# Sheet2-edgy.net
KiCad netlist of a schematic drawn in Altium Designer
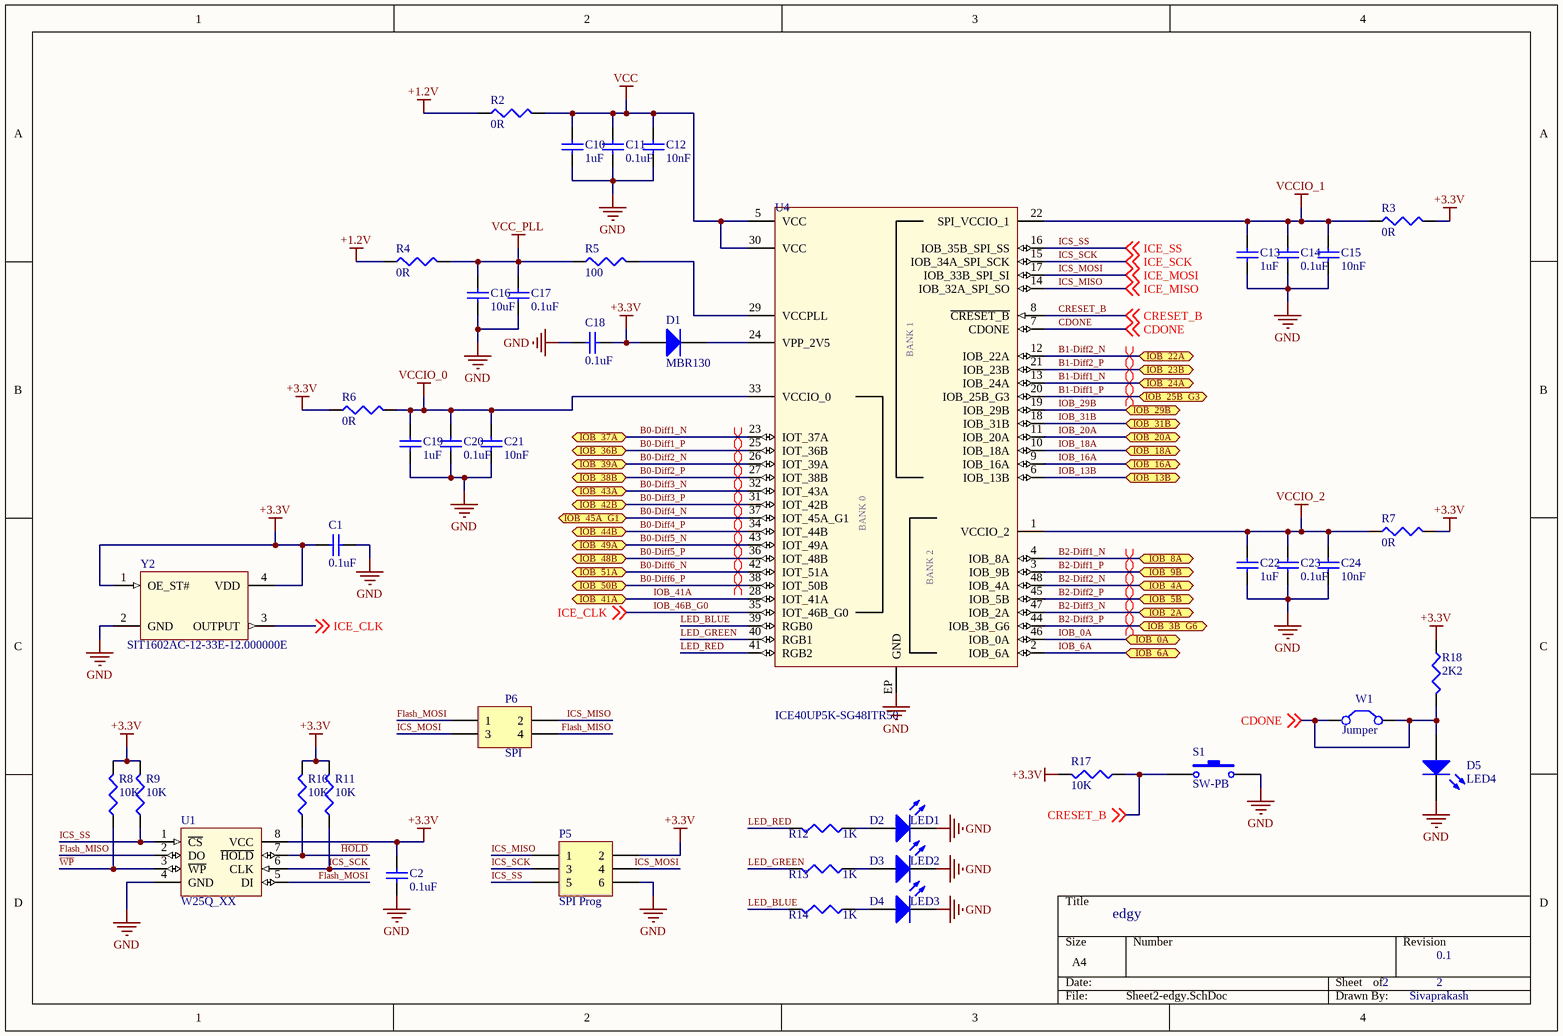
[diagram p0: Sheet2-edgy.SchDoc]

(export (version "E")
  (design (tool "Eeschema 10.0.6"))
  (components
    (comp (ref "C1")
      (value "0.1uF")
      (footprint "1608[0603]")
      (description "Capacitor (Semiconductor SIM Model)")
      (fields (field (name "PUBLISHER") "Altium Limited"))
      (libsource (lib "Miscellaneous Devices") (part "Cap Semi"))
    )
    (comp (ref "C2")
      (value "0.1uF")
      (footprint "1608[0603]")
      (description "Capacitor (Semiconductor SIM Model)")
      (fields (field (name "PUBLISHER") "Altium Limited"))
      (libsource (lib "Miscellaneous Devices") (part "Cap Semi"))
    )
    (comp (ref "C10")
      (value "1uF")
      (footprint "1608[0603]")
      (description "Capacitor (Semiconductor SIM Model)")
      (fields (field (name "PUBLISHER") "Altium Limited"))
      (libsource (lib "Miscellaneous Devices") (part "Cap Semi"))
    )
    (comp (ref "C11")
      (value "0.1uF")
      (footprint "1608[0603]")
      (description "Capacitor (Semiconductor SIM Model)")
      (fields (field (name "PUBLISHER") "Altium Limited"))
      (libsource (lib "Miscellaneous Devices") (part "Cap Semi"))
    )
    (comp (ref "C12")
      (value "10nF")
      (footprint "1608[0603]")
      (description "Capacitor (Semiconductor SIM Model)")
      (fields (field (name "PUBLISHER") "Altium Limited"))
      (libsource (lib "Miscellaneous Devices") (part "Cap Semi"))
    )
    (comp (ref "C13")
      (value "1uF")
      (footprint "1608[0603]")
      (description "Capacitor (Semiconductor SIM Model)")
      (fields (field (name "PUBLISHER") "Altium Limited"))
      (libsource (lib "Miscellaneous Devices") (part "Cap Semi"))
    )
    (comp (ref "C14")
      (value "0.1uF")
      (footprint "1608[0603]")
      (description "Capacitor (Semiconductor SIM Model)")
      (fields (field (name "PUBLISHER") "Altium Limited"))
      (libsource (lib "Miscellaneous Devices") (part "Cap Semi"))
    )
    (comp (ref "C15")
      (value "10nF")
      (footprint "1608[0603]")
      (description "Capacitor (Semiconductor SIM Model)")
      (fields (field (name "PUBLISHER") "Altium Limited"))
      (libsource (lib "Miscellaneous Devices") (part "Cap Semi"))
    )
    (comp (ref "C16")
      (value "10uF")
      (footprint "1608[0603]")
      (description "Capacitor (Semiconductor SIM Model)")
      (fields (field (name "PUBLISHER") "Altium Limited"))
      (libsource (lib "Miscellaneous Devices") (part "Cap Semi"))
    )
    (comp (ref "C17")
      (value "0.1uF")
      (footprint "1608[0603]")
      (description "Capacitor (Semiconductor SIM Model)")
      (fields (field (name "PUBLISHER") "Altium Limited"))
      (libsource (lib "Miscellaneous Devices") (part "Cap Semi"))
    )
    (comp (ref "C18")
      (value "0.1uF")
      (footprint "1608[0603]")
      (description "Capacitor (Semiconductor SIM Model)")
      (fields (field (name "PUBLISHER") "Altium Limited"))
      (libsource (lib "Miscellaneous Devices") (part "Cap Semi"))
    )
    (comp (ref "C19")
      (value "1uF")
      (footprint "1608[0603]")
      (description "Capacitor (Semiconductor SIM Model)")
      (fields (field (name "PUBLISHER") "Altium Limited"))
      (libsource (lib "Miscellaneous Devices") (part "Cap Semi"))
    )
    (comp (ref "C20")
      (value "0.1uF")
      (footprint "1608[0603]")
      (description "Capacitor (Semiconductor SIM Model)")
      (fields (field (name "PUBLISHER") "Altium Limited"))
      (libsource (lib "Miscellaneous Devices") (part "Cap Semi"))
    )
    (comp (ref "C21")
      (value "10nF")
      (footprint "1608[0603]")
      (description "Capacitor (Semiconductor SIM Model)")
      (fields (field (name "PUBLISHER") "Altium Limited"))
      (libsource (lib "Miscellaneous Devices") (part "Cap Semi"))
    )
    (comp (ref "C22")
      (value "1uF")
      (footprint "1608[0603]")
      (description "Capacitor (Semiconductor SIM Model)")
      (fields (field (name "PUBLISHER") "Altium Limited"))
      (libsource (lib "Miscellaneous Devices") (part "Cap Semi"))
    )
    (comp (ref "C23")
      (value "0.1uF")
      (footprint "1608[0603]")
      (description "Capacitor (Semiconductor SIM Model)")
      (fields (field (name "PUBLISHER") "Altium Limited"))
      (libsource (lib "Miscellaneous Devices") (part "Cap Semi"))
    )
    (comp (ref "C24")
      (value "10nF")
      (footprint "1608[0603]")
      (description "Capacitor (Semiconductor SIM Model)")
      (fields (field (name "PUBLISHER") "Altium Limited"))
      (libsource (lib "Miscellaneous Devices") (part "Cap Semi"))
    )
    (comp (ref "D1")
      (value "MBR130")
      (footprint "SOD_123")
      (description "Default Diode")
      (fields (field (name "PUBLISHER") "Altium Limited"))
      (libsource (lib "Miscellaneous Devices") (part "Diode"))
    )
    (comp (ref "D2")
      (value "LED1")
      (footprint "1608[0603]")
      (description "Typical BLUE SiC LED")
      (fields (field (name "PUBLISHER") "Altium Limited"))
      (libsource (lib "Miscellaneous Devices") (part "LED3"))
    )
    (comp (ref "D3")
      (value "LED2")
      (footprint "1608[0603]")
      (description "Typical BLUE SiC LED")
      (fields (field (name "PUBLISHER") "Altium Limited"))
      (libsource (lib "Miscellaneous Devices") (part "LED3"))
    )
    (comp (ref "D4")
      (value "LED3")
      (footprint "1608[0603]")
      (description "Typical BLUE SiC LED")
      (fields (field (name "PUBLISHER") "Altium Limited"))
      (libsource (lib "Miscellaneous Devices") (part "LED3"))
    )
    (comp (ref "D5")
      (value "LED4")
      (footprint "1608[0603]")
      (description "Typical BLUE SiC LED")
      (fields (field (name "PUBLISHER") "Altium Limited"))
      (libsource (lib "Miscellaneous Devices") (part "LED3"))
    )
    (comp (ref "P5")
      (value "SPI Prog")
      (footprint "2x3_2.54mm_pitch_header")
      (description "Header, 3-Pin, Dual row")
      (fields (field (name "PUBLISHER") "Altium Limited"))
      (libsource (lib "Miscellaneous Connectors") (part "Header 3X2"))
    )
    (comp (ref "P6")
      (value "SPI")
      (footprint "2x2_2.54mm_pitch_header")
      (description "Header, 2-Pin, Dual row")
      (fields (field (name "PUBLISHER") "Altium Limited"))
      (libsource (lib "Miscellaneous Connectors") (part "Header 2X2"))
    )
    (comp (ref "R2")
      (value "0R")
      (footprint "J1-0603")
      (description "Resistor")
      (fields (field (name "PUBLISHER") "Altium Limited"))
      (libsource (lib "Miscellaneous Devices") (part "Res3"))
    )
    (comp (ref "R3")
      (value "0R")
      (footprint "J1-0603")
      (description "Resistor")
      (fields (field (name "PUBLISHER") "Altium Limited"))
      (libsource (lib "Miscellaneous Devices") (part "Res3"))
    )
    (comp (ref "R4")
      (value "0R")
      (footprint "J1-0603")
      (description "Resistor")
      (fields (field (name "PUBLISHER") "Altium Limited"))
      (libsource (lib "Miscellaneous Devices") (part "Res3"))
    )
    (comp (ref "R5")
      (value "100")
      (footprint "J1-0603")
      (description "Resistor")
      (fields (field (name "PUBLISHER") "Altium Limited"))
      (libsource (lib "Miscellaneous Devices") (part "Res3"))
    )
    (comp (ref "R6")
      (value "0R")
      (footprint "J1-0603")
      (description "Resistor")
      (fields (field (name "PUBLISHER") "Altium Limited"))
      (libsource (lib "Miscellaneous Devices") (part "Res3"))
    )
    (comp (ref "R7")
      (value "0R")
      (footprint "J1-0603")
      (description "Resistor")
      (fields (field (name "PUBLISHER") "Altium Limited"))
      (libsource (lib "Miscellaneous Devices") (part "Res3"))
    )
    (comp (ref "R8")
      (value "10K")
      (footprint "J1-0603")
      (description "Resistor")
      (fields (field (name "PUBLISHER") "Altium Limited"))
      (libsource (lib "Miscellaneous Devices") (part "Res3"))
    )
    (comp (ref "R9")
      (value "10K")
      (footprint "J1-0603")
      (description "Resistor")
      (fields (field (name "PUBLISHER") "Altium Limited"))
      (libsource (lib "Miscellaneous Devices") (part "Res3"))
    )
    (comp (ref "R10")
      (value "10K")
      (footprint "J1-0603")
      (description "Resistor")
      (fields (field (name "PUBLISHER") "Altium Limited"))
      (libsource (lib "Miscellaneous Devices") (part "Res3"))
    )
    (comp (ref "R11")
      (value "10K")
      (footprint "J1-0603")
      (description "Resistor")
      (fields (field (name "PUBLISHER") "Altium Limited"))
      (libsource (lib "Miscellaneous Devices") (part "Res3"))
    )
    (comp (ref "R12")
      (value "1K")
      (footprint "J1-0603")
      (description "Resistor")
      (fields (field (name "PUBLISHER") "Altium Limited"))
      (libsource (lib "Miscellaneous Devices") (part "Res3"))
    )
    (comp (ref "R13")
      (value "1K")
      (footprint "J1-0603")
      (description "Resistor")
      (fields (field (name "PUBLISHER") "Altium Limited"))
      (libsource (lib "Miscellaneous Devices") (part "Res3"))
    )
    (comp (ref "R14")
      (value "1K")
      (footprint "J1-0603")
      (description "Resistor")
      (fields (field (name "PUBLISHER") "Altium Limited"))
      (libsource (lib "Miscellaneous Devices") (part "Res3"))
    )
    (comp (ref "R17")
      (value "10K")
      (footprint "J1-0603")
      (description "Resistor")
      (fields (field (name "PUBLISHER") "Altium Limited"))
      (libsource (lib "Miscellaneous Devices") (part "Res3"))
    )
    (comp (ref "R18")
      (value "2K2")
      (footprint "J1-0603")
      (description "Resistor")
      (fields (field (name "PUBLISHER") "Altium Limited"))
      (libsource (lib "Miscellaneous Devices") (part "Res3"))
    )
    (comp (ref "S1")
      (value "SW-PB")
      (footprint "Tact_Switch")
      (description "Switch")
      (fields (field (name "PUBLISHER") "Altium Limited"))
      (libsource (lib "Miscellaneous Devices") (part "SW-PB"))
    )
    (comp (ref "U1")
      (value "W25Q_XX")
      (footprint "SOIC-8_3.9x4.9mm_pitch1.27mm")
      (libsource (lib "edgy") (part "W25Q_XX"))
    )
    (comp (ref "U4")
      (value "ICE40UP5K-SG48ITR50")
      (footprint "*QFN50P700X700X100-49N_ICE40UP5K-SG48ITR50(Primary)")
      (description "iCE40 UltraPlusÂ™ 5280 LUTs 39 I/O 1.2 V Surface Mount FOPGA - QFN-48")
      (fields
        (field (name "DIGI-KEY_PART_NUMBER") "220-2145-1-ND")
        (field (name "MF") "Lattice Semiconductor")
      )
      (libsource (lib "edgy") (part "ICE40UP5K-SG48ITR50"))
    )
    (comp (ref "W1")
      (value "Jumper")
      (footprint "0402")
      (description "Jumper Wire")
      (fields (field (name "PUBLISHER") "Altium Limited"))
      (libsource (lib "Miscellaneous Devices") (part "Jumper"))
    )
    (comp (ref "Y2")
      (value "SIT1602AC-12-33E-12.000000E")
      (footprint "*OSCDFN320X250X80-4N")
      (fields (field (name "MANUFACTURER") "SiTime"))
      (libsource (lib "edgy") (part "SIT1602AC-12-33E-12.000000E"))
    )
  )
  (nets
    (net (code "1") (name "+1.2V") (class "Default")
      (node (ref "R2") (pin "1") (pinfunction "1_1") (pintype "passive"))
      (node (ref "R4") (pin "1") (pinfunction "1_1") (pintype "passive"))
    )
    (net (code "2") (name "+3.3V") (class "Default")
      (node (ref "C1") (pin "2") (pinfunction "2_2") (pintype "passive"))
      (node (ref "C18") (pin "1") (pinfunction "1_1") (pintype "passive"))
      (node (ref "C2") (pin "2") (pinfunction "2_2") (pintype "passive"))
      (node (ref "D1") (pin "1") (pinfunction "A_1") (pintype "passive"))
      (node (ref "P5") (pin "2") (pinfunction "2_2") (pintype "passive"))
      (node (ref "R10") (pin "1") (pinfunction "1_1") (pintype "passive"))
      (node (ref "R11") (pin "1") (pinfunction "1_1") (pintype "passive"))
      (node (ref "R17") (pin "2") (pinfunction "2_2") (pintype "passive"))
      (node (ref "R18") (pin "1") (pinfunction "1_1") (pintype "passive"))
      (node (ref "R3") (pin "1") (pinfunction "1_1") (pintype "passive"))
      (node (ref "R6") (pin "1") (pinfunction "1_1") (pintype "passive"))
      (node (ref "R7") (pin "1") (pinfunction "1_1") (pintype "passive"))
      (node (ref "R8") (pin "1") (pinfunction "1_1") (pintype "passive"))
      (node (ref "R9") (pin "1") (pinfunction "1_1") (pintype "passive"))
      (node (ref "U1") (pin "8") (pinfunction "VCC_8") (pintype "power_in"))
      (node (ref "Y2") (pin "1") (pinfunction "OE_ST#_1") (pintype "input"))
      (node (ref "Y2") (pin "4") (pinfunction "VDD_4") (pintype "power_in"))
    )
    (net (code "3") (name "/B0-Diff1_N") (class "Default")
      (node (ref "U4") (pin "23") (pinfunction "IOT_37A_23") (pintype "bidirectional"))
    )
    (net (code "4") (name "/B0-Diff1_P") (class "Default")
      (node (ref "U4") (pin "25") (pinfunction "IOT_36B_25") (pintype "bidirectional"))
    )
    (net (code "5") (name "/B0-Diff2_N") (class "Default")
      (node (ref "U4") (pin "26") (pinfunction "IOT_39A_26") (pintype "bidirectional"))
    )
    (net (code "6") (name "/B0-Diff2_P") (class "Default")
      (node (ref "U4") (pin "27") (pinfunction "IOT_38B_27") (pintype "bidirectional"))
    )
    (net (code "7") (name "/B0-Diff3_N") (class "Default")
      (node (ref "U4") (pin "32") (pinfunction "IOT_43A_32") (pintype "bidirectional"))
    )
    (net (code "8") (name "/B0-Diff3_P") (class "Default")
      (node (ref "U4") (pin "31") (pinfunction "IOT_42B_31") (pintype "bidirectional"))
    )
    (net (code "9") (name "/B0-Diff4_N") (class "Default")
      (node (ref "U4") (pin "37") (pinfunction "IOT_45A_G1_37") (pintype "bidirectional"))
    )
    (net (code "10") (name "/B0-Diff4_P") (class "Default")
      (node (ref "U4") (pin "34") (pinfunction "IOT_44B_34") (pintype "bidirectional"))
    )
    (net (code "11") (name "/B0-Diff5_N") (class "Default")
      (node (ref "U4") (pin "43") (pinfunction "IOT_49A_43") (pintype "bidirectional"))
    )
    (net (code "12") (name "/B0-Diff5_P") (class "Default")
      (node (ref "U4") (pin "36") (pinfunction "IOT_48B_36") (pintype "bidirectional"))
    )
    (net (code "13") (name "/B0-Diff6_N") (class "Default")
      (node (ref "U4") (pin "42") (pinfunction "IOT_51A_42") (pintype "bidirectional"))
    )
    (net (code "14") (name "/B0-Diff6_P") (class "Default")
      (node (ref "U4") (pin "38") (pinfunction "IOT_50B_38") (pintype "bidirectional"))
    )
    (net (code "15") (name "/B1-Diff1_N") (class "Default")
      (node (ref "U4") (pin "13") (pinfunction "IOB_24A_13") (pintype "bidirectional"))
    )
    (net (code "16") (name "/B1-Diff1_P") (class "Default")
      (node (ref "U4") (pin "20") (pinfunction "IOB_25B_G3_20") (pintype "bidirectional"))
    )
    (net (code "17") (name "/B1-Diff2_N") (class "Default")
      (node (ref "U4") (pin "12") (pinfunction "IOB_22A_12") (pintype "bidirectional"))
    )
    (net (code "18") (name "/B1-Diff2_P") (class "Default")
      (node (ref "U4") (pin "21") (pinfunction "IOB_23B_21") (pintype "bidirectional"))
    )
    (net (code "19") (name "/B2-Diff1_N") (class "Default")
      (node (ref "U4") (pin "4") (pinfunction "IOB_8A_4") (pintype "bidirectional"))
    )
    (net (code "20") (name "/B2-Diff1_P") (class "Default")
      (node (ref "U4") (pin "3") (pinfunction "IOB_9B_3") (pintype "bidirectional"))
    )
    (net (code "21") (name "/B2-Diff2_N") (class "Default")
      (node (ref "U4") (pin "48") (pinfunction "IOB_4A_48") (pintype "bidirectional"))
    )
    (net (code "22") (name "/B2-Diff2_P") (class "Default")
      (node (ref "U4") (pin "45") (pinfunction "IOB_5B_45") (pintype "bidirectional"))
    )
    (net (code "23") (name "/B2-Diff3_N") (class "Default")
      (node (ref "U4") (pin "47") (pinfunction "IOB_2A_47") (pintype "bidirectional"))
    )
    (net (code "24") (name "/B2-Diff3_P") (class "Default")
      (node (ref "U4") (pin "44") (pinfunction "IOB_3B_G6_44") (pintype "bidirectional"))
    )
    (net (code "25") (name "/Flash_MISO") (class "Default")
      (node (ref "P6") (pin "4") (pinfunction "4_4") (pintype "passive"))
      (node (ref "U1") (pin "2") (pinfunction "DO_2") (pintype "bidirectional"))
    )
    (net (code "26") (name "/Flash_MOSI") (class "Default")
      (node (ref "P6") (pin "1") (pinfunction "1_1") (pintype "passive"))
      (node (ref "U1") (pin "5") (pinfunction "DI_5") (pintype "bidirectional"))
    )
    (net (code "27") (name "/IOB_0A") (class "Default")
      (node (ref "U4") (pin "46") (pinfunction "IOB_0A_46") (pintype "bidirectional"))
    )
    (net (code "28") (name "/IOB_6A") (class "Default")
      (node (ref "U4") (pin "2") (pinfunction "IOB_6A_2") (pintype "bidirectional"))
    )
    (net (code "29") (name "/IOB_13B") (class "Default")
      (node (ref "U4") (pin "6") (pinfunction "IOB_13B_6") (pintype "bidirectional"))
    )
    (net (code "30") (name "/IOB_16A") (class "Default")
      (node (ref "U4") (pin "9") (pinfunction "IOB_16A_9") (pintype "bidirectional"))
    )
    (net (code "31") (name "/IOB_18A") (class "Default")
      (node (ref "U4") (pin "10") (pinfunction "IOB_18A_10") (pintype "bidirectional"))
    )
    (net (code "32") (name "/IOB_20A") (class "Default")
      (node (ref "U4") (pin "11") (pinfunction "IOB_20A_11") (pintype "bidirectional"))
    )
    (net (code "33") (name "/IOB_29B") (class "Default")
      (node (ref "U4") (pin "19") (pinfunction "IOB_29B_19") (pintype "bidirectional"))
    )
    (net (code "34") (name "/IOB_31B") (class "Default")
      (node (ref "U4") (pin "18") (pinfunction "IOB_31B_18") (pintype "bidirectional"))
    )
    (net (code "35") (name "/IOB_41A") (class "Default")
      (node (ref "U4") (pin "28") (pinfunction "IOT_41A_28") (pintype "bidirectional"))
    )
    (net (code "36") (name "/LED_BLUE") (class "Default")
      (node (ref "R14") (pin "2") (pinfunction "2_2") (pintype "passive"))
      (node (ref "U4") (pin "39") (pinfunction "RGB0_39") (pintype "bidirectional"))
    )
    (net (code "37") (name "/LED_GREEN") (class "Default")
      (node (ref "R13") (pin "2") (pinfunction "2_2") (pintype "passive"))
      (node (ref "U4") (pin "40") (pinfunction "RGB1_40") (pintype "bidirectional"))
    )
    (net (code "38") (name "/LED_RED") (class "Default")
      (node (ref "R12") (pin "2") (pinfunction "2_2") (pintype "passive"))
      (node (ref "U4") (pin "41") (pinfunction "RGB2_41") (pintype "bidirectional"))
    )
    (net (code "39") (name "/~{HOLD}") (class "Default")
      (node (ref "R10") (pin "2") (pinfunction "2_2") (pintype "passive"))
      (node (ref "U1") (pin "7") (pinfunction "~{HOLD}_7") (pintype "bidirectional"))
    )
    (net (code "40") (name "/~{WP}") (class "Default")
      (node (ref "R8") (pin "2") (pinfunction "2_2") (pintype "passive"))
      (node (ref "U1") (pin "3") (pinfunction "~{WP}_3") (pintype "bidirectional"))
    )
    (net (code "41") (name "CDONE") (class "Default")
      (node (ref "D5") (pin "1") (pinfunction "A_1") (pintype "passive"))
      (node (ref "R18") (pin "2") (pinfunction "2_2") (pintype "passive"))
      (node (ref "U4") (pin "7") (pinfunction "CDONE_7") (pintype "bidirectional"))
      (node (ref "W1") (pin "1") (pinfunction "C1_1") (pintype "passive"))
      (node (ref "W1") (pin "2") (pinfunction "C2_2") (pintype "passive"))
    )
    (net (code "42") (name "CRESET_B") (class "Default")
      (node (ref "R17") (pin "1") (pinfunction "1_1") (pintype "passive"))
      (node (ref "S1") (pin "1") (pinfunction "1_1") (pintype "passive"))
      (node (ref "U4") (pin "8") (pinfunction "~{CRESET_B}_8") (pintype "input"))
    )
    (net (code "43") (name "GND") (class "Default")
      (node (ref "C1") (pin "1") (pinfunction "1_1") (pintype "passive"))
      (node (ref "C10") (pin "1") (pinfunction "1_1") (pintype "passive"))
      (node (ref "C11") (pin "1") (pinfunction "1_1") (pintype "passive"))
      (node (ref "C12") (pin "1") (pinfunction "1_1") (pintype "passive"))
      (node (ref "C13") (pin "1") (pinfunction "1_1") (pintype "passive"))
      (node (ref "C14") (pin "1") (pinfunction "1_1") (pintype "passive"))
      (node (ref "C15") (pin "1") (pinfunction "1_1") (pintype "passive"))
      (node (ref "C16") (pin "1") (pinfunction "1_1") (pintype "passive"))
      (node (ref "C17") (pin "1") (pinfunction "1_1") (pintype "passive"))
      (node (ref "C18") (pin "2") (pinfunction "2_2") (pintype "passive"))
      (node (ref "C19") (pin "1") (pinfunction "1_1") (pintype "passive"))
      (node (ref "C2") (pin "1") (pinfunction "1_1") (pintype "passive"))
      (node (ref "C20") (pin "1") (pinfunction "1_1") (pintype "passive"))
      (node (ref "C21") (pin "1") (pinfunction "1_1") (pintype "passive"))
      (node (ref "C22") (pin "1") (pinfunction "1_1") (pintype "passive"))
      (node (ref "C23") (pin "1") (pinfunction "1_1") (pintype "passive"))
      (node (ref "C24") (pin "1") (pinfunction "1_1") (pintype "passive"))
      (node (ref "D2") (pin "2") (pinfunction "K_2") (pintype "passive"))
      (node (ref "D3") (pin "2") (pinfunction "K_2") (pintype "passive"))
      (node (ref "D4") (pin "2") (pinfunction "K_2") (pintype "passive"))
      (node (ref "D5") (pin "2") (pinfunction "K_2") (pintype "passive"))
      (node (ref "P5") (pin "6") (pinfunction "6_6") (pintype "passive"))
      (node (ref "S1") (pin "2") (pinfunction "2_2") (pintype "passive"))
      (node (ref "U1") (pin "4") (pinfunction "GND_4") (pintype "power_in"))
      (node (ref "U4") (pin "EP") (pinfunction "GND_EP") (pintype "power_in"))
      (node (ref "Y2") (pin "2") (pinfunction "GND_2") (pintype "power_in"))
    )
    (net (code "44") (name "ICE_CLK") (class "Default")
      (node (ref "U4") (pin "35") (pinfunction "IOT_46B_G0_35") (pintype "bidirectional"))
      (node (ref "Y2") (pin "3") (pinfunction "OUTPUT_3") (pintype "output"))
    )
    (net (code "45") (name "ICE_MISO") (class "Default")
      (node (ref "P5") (pin "1") (pinfunction "1_1") (pintype "passive"))
      (node (ref "P6") (pin "2") (pinfunction "2_2") (pintype "passive"))
      (node (ref "U4") (pin "14") (pinfunction "IOB_32A_SPI_SO_14") (pintype "bidirectional"))
    )
    (net (code "46") (name "ICE_MOSI") (class "Default")
      (node (ref "P5") (pin "4") (pinfunction "4_4") (pintype "passive"))
      (node (ref "P6") (pin "3") (pinfunction "3_3") (pintype "passive"))
      (node (ref "U4") (pin "17") (pinfunction "IOB_33B_SPI_SI_17") (pintype "bidirectional"))
    )
    (net (code "47") (name "ICE_SCK") (class "Default")
      (node (ref "P5") (pin "3") (pinfunction "3_3") (pintype "passive"))
      (node (ref "R11") (pin "2") (pinfunction "2_2") (pintype "passive"))
      (node (ref "U1") (pin "6") (pinfunction "CLK_6") (pintype "input"))
      (node (ref "U4") (pin "15") (pinfunction "IOB_34A_SPI_SCK_15") (pintype "bidirectional"))
    )
    (net (code "48") (name "ICE_SS") (class "Default")
      (node (ref "P5") (pin "5") (pinfunction "5_5") (pintype "passive"))
      (node (ref "R9") (pin "2") (pinfunction "2_2") (pintype "passive"))
      (node (ref "U1") (pin "1") (pinfunction "~{CS}_1") (pintype "input"))
      (node (ref "U4") (pin "16") (pinfunction "IOB_35B_SPI_SS_16") (pintype "bidirectional"))
    )
    (net (code "49") (name "Net-(D1-K)") (class "Default")
      (node (ref "D1") (pin "2") (pinfunction "K_2") (pintype "passive"))
      (node (ref "U4") (pin "24") (pinfunction "VPP_2V5_24") (pintype "power_in"))
    )
    (net (code "50") (name "Net-(D2-A)") (class "Default")
      (node (ref "D2") (pin "1") (pinfunction "A_1") (pintype "passive"))
      (node (ref "R12") (pin "1") (pinfunction "1_1") (pintype "passive"))
    )
    (net (code "51") (name "Net-(D3-A)") (class "Default")
      (node (ref "D3") (pin "1") (pinfunction "A_1") (pintype "passive"))
      (node (ref "R13") (pin "1") (pinfunction "1_1") (pintype "passive"))
    )
    (net (code "52") (name "Net-(D4-A)") (class "Default")
      (node (ref "D4") (pin "1") (pinfunction "A_1") (pintype "passive"))
      (node (ref "R14") (pin "1") (pinfunction "1_1") (pintype "passive"))
    )
    (net (code "53") (name "Net-(U4-VCCPLL)") (class "Default")
      (node (ref "R5") (pin "2") (pinfunction "2_2") (pintype "passive"))
      (node (ref "U4") (pin "29") (pinfunction "VCCPLL_29") (pintype "power_in"))
    )
    (net (code "54") (name "VCC") (class "Default")
      (node (ref "C10") (pin "2") (pinfunction "2_2") (pintype "passive"))
      (node (ref "C11") (pin "2") (pinfunction "2_2") (pintype "passive"))
      (node (ref "C12") (pin "2") (pinfunction "2_2") (pintype "passive"))
      (node (ref "R2") (pin "2") (pinfunction "2_2") (pintype "passive"))
      (node (ref "U4") (pin "30") (pinfunction "VCC_30") (pintype "power_in"))
      (node (ref "U4") (pin "5") (pinfunction "VCC_5") (pintype "power_in"))
    )
    (net (code "55") (name "VCCIO_0") (class "Default")
      (node (ref "C19") (pin "2") (pinfunction "2_2") (pintype "passive"))
      (node (ref "C20") (pin "2") (pinfunction "2_2") (pintype "passive"))
      (node (ref "C21") (pin "2") (pinfunction "2_2") (pintype "passive"))
      (node (ref "R6") (pin "2") (pinfunction "2_2") (pintype "passive"))
      (node (ref "U4") (pin "33") (pinfunction "VCCIO_0_33") (pintype "power_in"))
    )
    (net (code "56") (name "VCCIO_1") (class "Default")
      (node (ref "C13") (pin "2") (pinfunction "2_2") (pintype "passive"))
      (node (ref "C14") (pin "2") (pinfunction "2_2") (pintype "passive"))
      (node (ref "C15") (pin "2") (pinfunction "2_2") (pintype "passive"))
      (node (ref "R3") (pin "2") (pinfunction "2_2") (pintype "passive"))
      (node (ref "U4") (pin "22") (pinfunction "SPI_VCCIO_1_22") (pintype "power_in"))
    )
    (net (code "57") (name "VCCIO_2") (class "Default")
      (node (ref "C22") (pin "2") (pinfunction "2_2") (pintype "passive"))
      (node (ref "C23") (pin "2") (pinfunction "2_2") (pintype "passive"))
      (node (ref "C24") (pin "2") (pinfunction "2_2") (pintype "passive"))
      (node (ref "R7") (pin "2") (pinfunction "2_2") (pintype "passive"))
      (node (ref "U4") (pin "1") (pinfunction "VCCIO_2_1") (pintype "power_in"))
    )
    (net (code "58") (name "VCC_PLL") (class "Default")
      (node (ref "C16") (pin "2") (pinfunction "2_2") (pintype "passive"))
      (node (ref "C17") (pin "2") (pinfunction "2_2") (pintype "passive"))
      (node (ref "R4") (pin "2") (pinfunction "2_2") (pintype "passive"))
      (node (ref "R5") (pin "1") (pinfunction "1_1") (pintype "passive"))
    )
  )
)
